# Low-Voltage-5V-Step-Up-Converter.net
KiCad netlist of a schematic drawn in Altium Designer
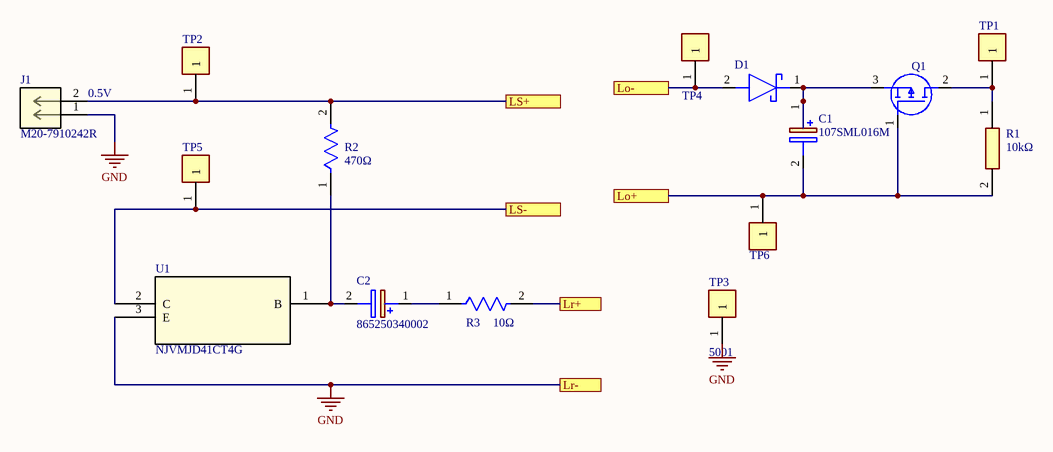
[diagram p0: Low-Voltage-5V-Step-Up-Converter.SchDoc]

(export (version "E")
  (design (tool "Eeschema 10.0.6"))
  (components
    (comp (ref "C1")
      (value "107SML016M")
      (footprint "SamacSys:CAPAE660X570N")
      (description "Capacitor Polarised")
      (fields (field (name "MOUSER PART NUMBER") "598-107SML016M"))
      (libsource (lib "SamacSys") (part "107SML016M"))
    )
    (comp (ref "C2")
      (value "865250340002")
      (footprint "SamacSys:CAPAE430X550N")
      (description "Capacitor Polarised")
      (fields (field (name "MOUSER PART NUMBER") "710-865250340002"))
      (libsource (lib "SamacSys") (part "865250340002"))
    )
    (comp (ref "D1")
      (value "B2100A-13-F")
      (footprint "SamacSys:DIOM5226X230N")
      (description "Schottky Diode")
      (fields (field (name "MOUSER PART NUMBER") "621-B2100A-13-F"))
      (libsource (lib "SamacSys") (part "B2100A-13-F"))
    )
    (comp (ref "J1")
      (value "M20-7910242R")
      (footprint "M20-7910242R:CONN2_910242R_HRW")
      (description "No Description Available")
      (fields (field (name "COPYRIGHT") "Copyright (C) 2023 Ultra Librarian. All rights reserved."))
      (libsource (lib "M20-7910242R") (part "M20-7910242R"))
    )
    (comp (ref "Q1")
      (value "IRF9Z34NSTRLPBF")
      (footprint "SamacSys:IRF2804STRLPBF")
      (description "MOSFET (P-Channel)")
      (fields (field (name "MOUSER PART NUMBER") "942-IRF9Z34NSTRLPBF"))
      (libsource (lib "SamacSys") (part "IRF9Z34NSTRLPBF"))
    )
    (comp (ref "R1")
      (value "RC1206JR-0710KP")
      (footprint "SamacSys:RESC3116X65N")
      (description "Resistor")
      (fields (field (name "RESISTANCE") "10kΩ"))
      (libsource (lib "SamacSys") (part "RC1206JR-0710KP"))
    )
    (comp (ref "R2")
      (value "RMCF1206JT470R")
      (footprint "FP-RMCF1206-MFG")
      (description "470Ω ±5% 0.25W 1206 Thick Film Chip Resistor AEC-Q200 compliant")
      (fields (field (name "RESISTANCE") "470Ω") (field (name "TOLERANCE") "5%"))
      (libsource (lib "Altium Content Vault") (part "1029c3af85768c4190bb7ad29bc67b5"))
    )
    (comp (ref "R3")
      (value "RNCP0805FTD10R0")
      (footprint "FP-RNCP0805-IPC_C")
      (description "10Ω ±1% 0.25W 0805 High Power Anti-Sulfur Thin Film Chip Resistor")
      (fields (field (name "TOLERANCE") "1%") (field (name "RESISTANCE") "10Ω"))
      (libsource (lib "Altium Content Vault") (part "1029c3af85768c4190bb7ad29bc67b5"))
    )
    (comp (ref "TP1")
      (value "5001")
      (footprint "FP-5001-MFG")
      (description "PC TEST POINT MINIATURE BLACK")
      (libsource (lib "Altium Content Vault") (part "1e4615820a309e3ce90f9e6d957b7fa"))
    )
    (comp (ref "TP2")
      (value "5001")
      (footprint "FP-5001-MFG")
      (description "PC TEST POINT MINIATURE BLACK")
      (libsource (lib "Altium Content Vault") (part "1e4615820a309e3ce90f9e6d957b7fa"))
    )
    (comp (ref "TP3")
      (value "5001")
      (footprint "FP-5001-MFG")
      (description "PC TEST POINT MINIATURE BLACK")
      (libsource (lib "Altium Content Vault") (part "1e4615820a309e3ce90f9e6d957b7fa"))
    )
    (comp (ref "TP4")
      (value "5001")
      (footprint "FP-5001-MFG")
      (description "PC TEST POINT MINIATURE BLACK")
      (libsource (lib "Altium Content Vault") (part "1e4615820a309e3ce90f9e6d957b7fa"))
    )
    (comp (ref "TP5")
      (value "5001")
      (footprint "FP-5001-MFG")
      (description "PC TEST POINT MINIATURE BLACK")
      (libsource (lib "Altium Content Vault") (part "1e4615820a309e3ce90f9e6d957b7fa"))
    )
    (comp (ref "TP6")
      (value "5001")
      (footprint "FP-5001-MFG")
      (description "PC TEST POINT MINIATURE BLACK")
      (libsource (lib "") (part "1e4615820a309e3ce90f9e6d957b7fa_1"))
    )
    (comp (ref "U1")
      (value "NJVMJD41CT4G")
      (footprint "NJVMJD41CT4G:DPAK-4_6P22X6P73_ONS")
      (description "No Description Available")
      (fields (field (name "COPYRIGHT") "Copyright (C) 2023 Ultra Librarian. All rights reserved."))
      (libsource (lib "NJVMJD41CT4G") (part "NJVMJD41CT4G"))
    )
  )
  (nets
    (net (code "1") (name "/LS+") (class "Default")
      (node (ref "J1") (pin "2") (pinfunction "2_2") (pintype "passive"))
      (node (ref "R2") (pin "2") (pinfunction "2_2") (pintype "passive"))
      (node (ref "TP2") (pin "1") (pinfunction "1_1") (pintype "passive"))
    )
    (net (code "2") (name "/LS-") (class "Default")
      (node (ref "TP5") (pin "1") (pinfunction "1_1") (pintype "passive"))
      (node (ref "U1") (pin "2") (pinfunction "C_2") (pintype "passive"))
    )
    (net (code "3") (name "/Lo+") (class "Default")
      (node (ref "C1") (pin "2") (pinfunction "-_2") (pintype "passive"))
      (node (ref "Q1") (pin "1") (pinfunction "G_1") (pintype "passive"))
      (node (ref "R1") (pin "2") (pinfunction "2_2") (pintype "passive"))
      (node (ref "TP6") (pin "1") (pinfunction "1_1") (pintype "passive"))
    )
    (net (code "4") (name "/Lo-") (class "Default")
      (node (ref "D1") (pin "2") (pinfunction "A_2") (pintype "passive"))
      (node (ref "TP4") (pin "1") (pinfunction "1_1") (pintype "passive"))
    )
    (net (code "5") (name "/Lr+") (class "Default")
      (node (ref "R3") (pin "2") (pinfunction "2_2") (pintype "passive"))
    )
    (net (code "6") (name "GND") (class "Default")
      (node (ref "J1") (pin "1") (pinfunction "1_1") (pintype "passive"))
      (node (ref "TP3") (pin "1") (pinfunction "1_1") (pintype "passive"))
      (node (ref "U1") (pin "3") (pinfunction "E_3") (pintype "passive"))
    )
    (net (code "7") (name "Net-(C1-+)") (class "Default")
      (node (ref "C1") (pin "1") (pinfunction "+_1") (pintype "passive"))
      (node (ref "D1") (pin "1") (pinfunction "K_1") (pintype "passive"))
      (node (ref "Q1") (pin "3") (pinfunction "S_3") (pintype "passive"))
    )
    (net (code "8") (name "Net-(C2-+)") (class "Default")
      (node (ref "C2") (pin "1") (pinfunction "+_1") (pintype "passive"))
      (node (ref "R3") (pin "1") (pinfunction "1_1") (pintype "passive"))
    )
    (net (code "9") (name "Net-(C2--)") (class "Default")
      (node (ref "C2") (pin "2") (pinfunction "-_2") (pintype "passive"))
      (node (ref "R2") (pin "1") (pinfunction "1_1") (pintype "passive"))
      (node (ref "U1") (pin "1") (pinfunction "B_1") (pintype "passive"))
    )
    (net (code "10") (name "Net-(Q1-D)") (class "Default")
      (node (ref "Q1") (pin "2") (pinfunction "D_2") (pintype "passive"))
      (node (ref "R1") (pin "1") (pinfunction "1_1") (pintype "passive"))
      (node (ref "TP1") (pin "1") (pinfunction "1_1") (pintype "passive"))
    )
  )
)
